# Pow_bank.net
KiCad netlist of a schematic drawn in EAGLE
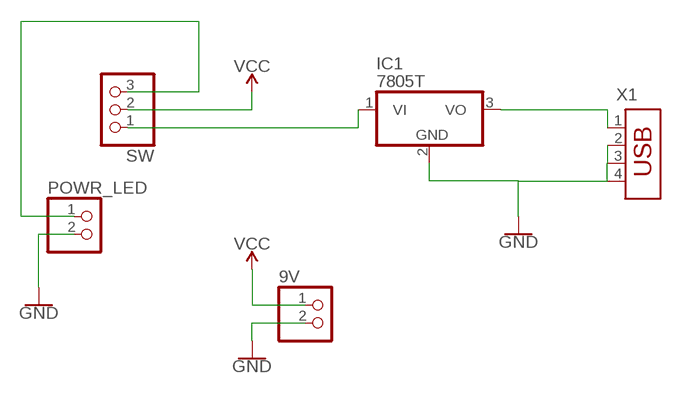
[diagram p0: schematic, sheet 1]

(export (version "E")
  (design (tool "Eeschema 10.0.6"))
  (components
    (comp (ref "9V")
      (value "PINHD-1X2")
      (footprint "eagle-import:1X02")
      (libsource (lib "eagle-import") (part "PINHD-1X2"))
    )
    (comp (ref "IC1")
      (value "7805T")
      (footprint "eagle-import:TO220H")
      (libsource (lib "eagle-import") (part "78T05"))
    )
    (comp (ref "POWR_LED")
      (value "PINHD-1X2")
      (footprint "eagle-import:1X02")
      (libsource (lib "eagle-import") (part "PINHD-1X2"))
    )
    (comp (ref "SW")
      (value "PINHD-1X3")
      (footprint "eagle-import:1X03")
      (libsource (lib "eagle-import") (part "PINHD-1X3"))
    )
    (comp (ref "X1")
      (value "USB-787616")
      (footprint "eagle-import:USB")
      (libsource (lib "eagle-import") (part "USB-787616"))
    )
  )
  (nets
    (net (code "1") (name "GND") (class "Default")
      (node (ref "9V") (pin "2") (pinfunction "2_2") (pintype "passive"))
      (node (ref "IC1") (pin "2") (pinfunction "GND_2") (pintype "passive"))
      (node (ref "POWR_LED") (pin "2") (pinfunction "2_2") (pintype "passive"))
      (node (ref "X1") (pin "2") (pinfunction "2_2") (pintype "passive"))
      (node (ref "X1") (pin "3") (pinfunction "3_3") (pintype "passive"))
      (node (ref "X1") (pin "4") (pinfunction "4_4") (pintype "passive"))
    )
    (net (code "2") (name "Net-(IC1-VI)") (class "Default")
      (node (ref "IC1") (pin "1") (pinfunction "VI_1") (pintype "input"))
      (node (ref "SW") (pin "1") (pinfunction "1_1") (pintype "passive"))
    )
    (net (code "3") (name "Net-(IC1-VO)") (class "Default")
      (node (ref "IC1") (pin "3") (pinfunction "VO_3") (pintype "passive"))
      (node (ref "X1") (pin "1") (pinfunction "1_1") (pintype "passive"))
    )
    (net (code "4") (name "Net-(POWR_LED-Pad1)") (class "Default")
      (node (ref "POWR_LED") (pin "1") (pinfunction "1_1") (pintype "passive"))
      (node (ref "SW") (pin "3") (pinfunction "3_3") (pintype "passive"))
    )
    (net (code "5") (name "VCC") (class "Default")
      (node (ref "9V") (pin "1") (pinfunction "1_1") (pintype "passive"))
      (node (ref "SW") (pin "2") (pinfunction "2_2") (pintype "passive"))
    )
  )
)
